# strobe_tuner.net
KiCad netlist of a schematic drawn in EAGLE
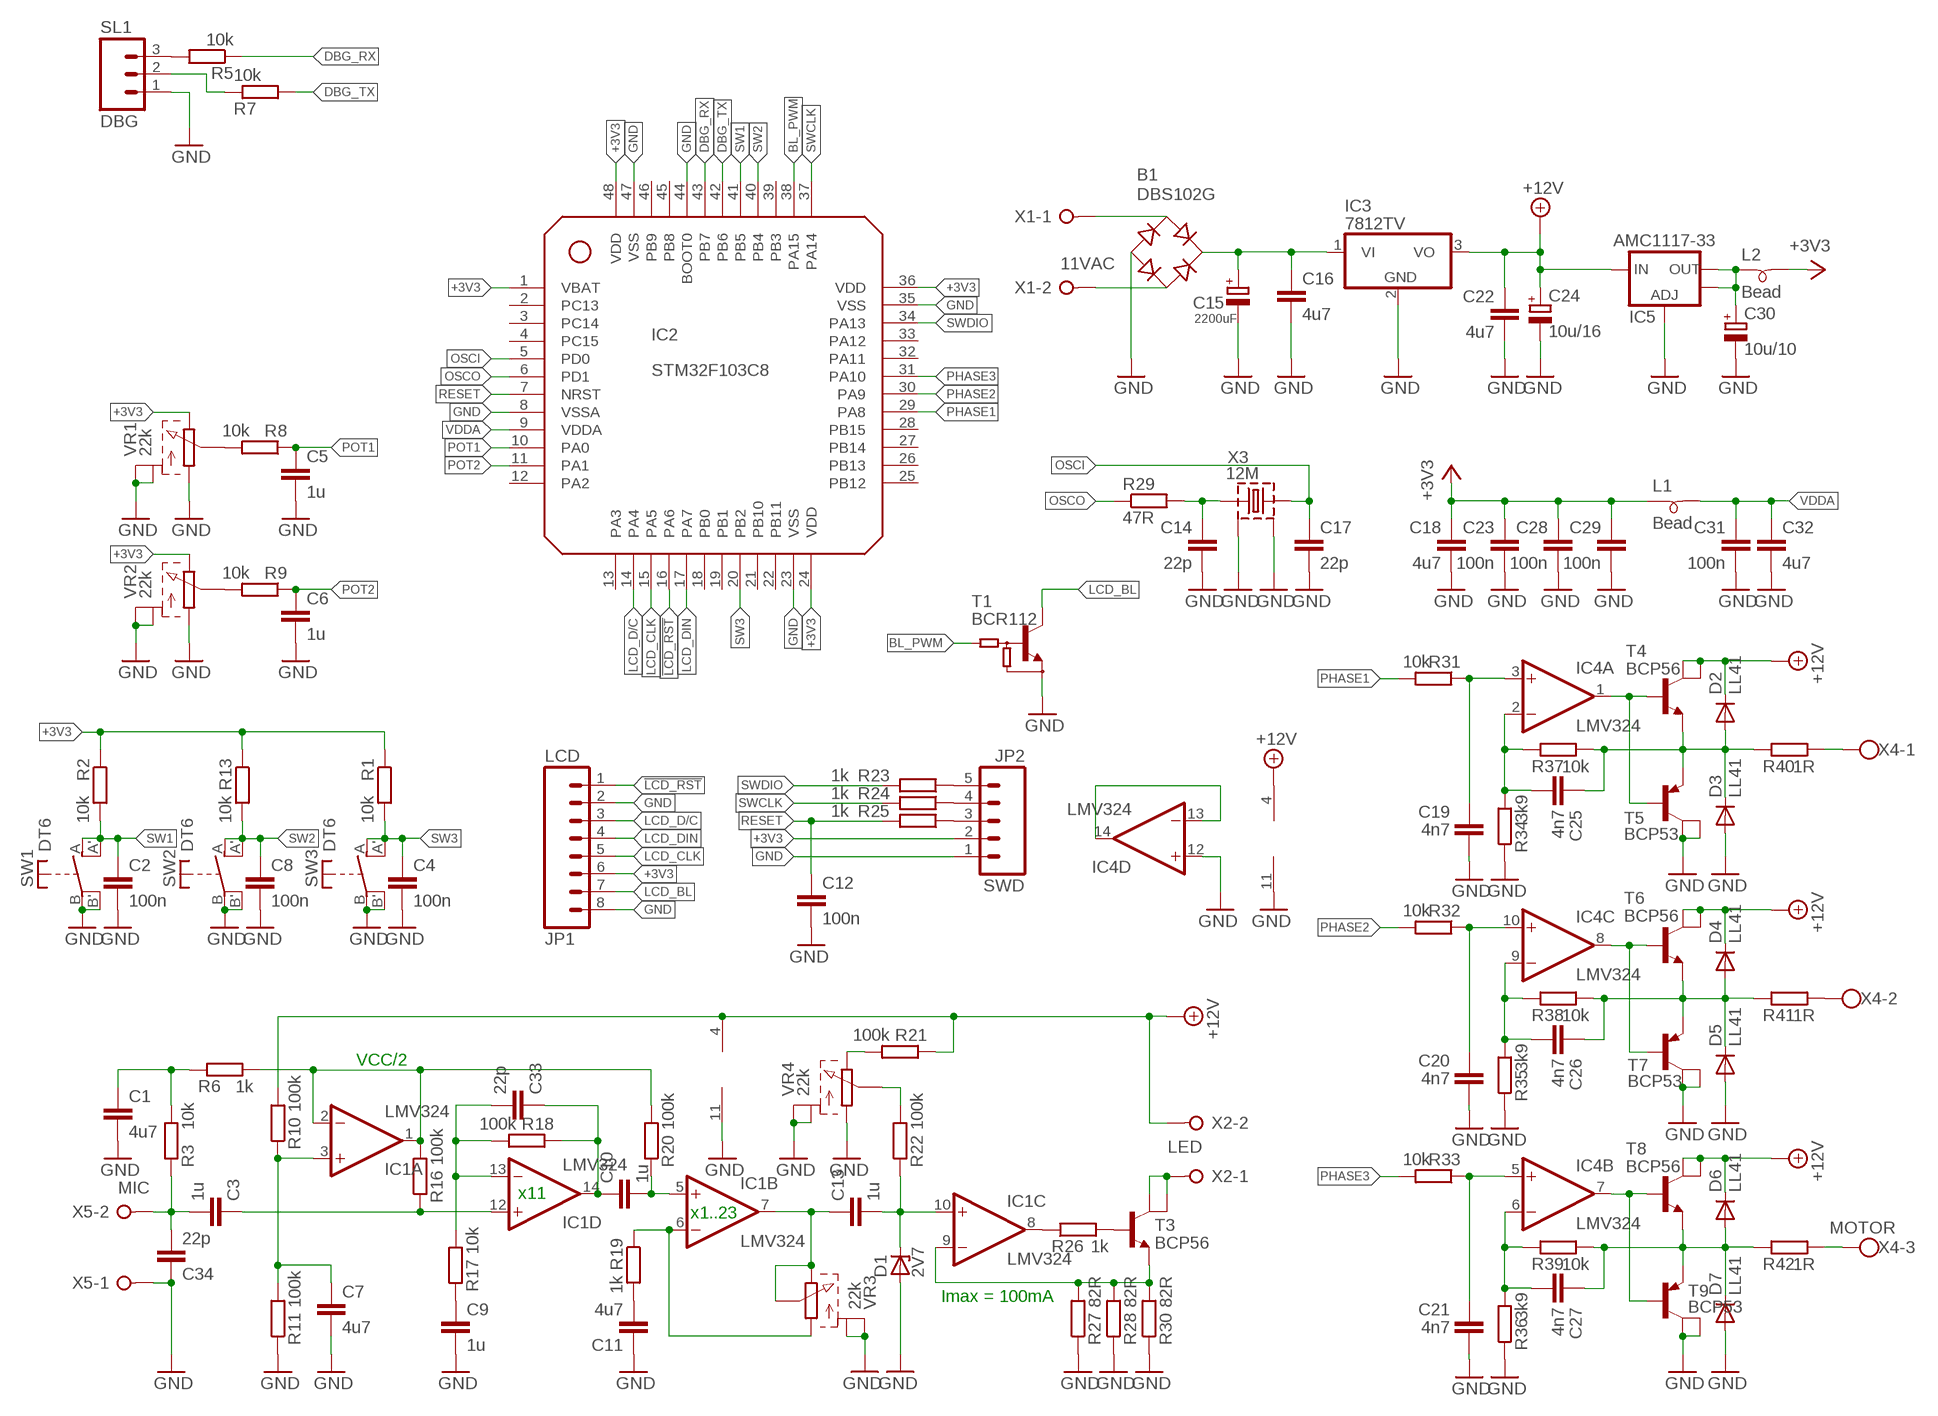
[diagram p0: schematic, sheet 1]

(export (version "E")
  (design (tool "Eeschema 10.0.6"))
  (components
    (comp (ref "B1")
      (value "DBS102G")
      (footprint "eagle-import:DBS")
      (libsource (lib "eagle-import") (part "DB?GS102"))
    )
    (comp (ref "C1")
      (value "4u7")
      (footprint "eagle-import:1206")
      (libsource (lib "eagle-import") (part "1206_CAP"))
    )
    (comp (ref "C2")
      (value "100n")
      (footprint "eagle-import:0805")
      (libsource (lib "eagle-import") (part "0805_CAP"))
    )
    (comp (ref "C3")
      (value "1u")
      (footprint "eagle-import:1206")
      (libsource (lib "eagle-import") (part "1206_CAP"))
    )
    (comp (ref "C4")
      (value "100n")
      (footprint "eagle-import:0805")
      (libsource (lib "eagle-import") (part "0805_CAP"))
    )
    (comp (ref "C5")
      (value "1u")
      (footprint "eagle-import:1206")
      (libsource (lib "eagle-import") (part "1206_CAP"))
    )
    (comp (ref "C6")
      (value "1u")
      (footprint "eagle-import:1206")
      (libsource (lib "eagle-import") (part "1206_CAP"))
    )
    (comp (ref "C7")
      (value "4u7")
      (footprint "eagle-import:1206")
      (libsource (lib "eagle-import") (part "1206_CAP"))
    )
    (comp (ref "C8")
      (value "100n")
      (footprint "eagle-import:0805")
      (libsource (lib "eagle-import") (part "0805_CAP"))
    )
    (comp (ref "C9")
      (value "1u")
      (footprint "eagle-import:1206")
      (libsource (lib "eagle-import") (part "1206_CAP"))
    )
    (comp (ref "C10")
      (value "1u")
      (footprint "eagle-import:1206")
      (libsource (lib "eagle-import") (part "1206_CAP"))
    )
    (comp (ref "C11")
      (value "4u7")
      (footprint "eagle-import:1206")
      (libsource (lib "eagle-import") (part "1206_CAP"))
    )
    (comp (ref "C12")
      (value "100n")
      (footprint "eagle-import:0805")
      (libsource (lib "eagle-import") (part "0805_CAP"))
    )
    (comp (ref "C13")
      (value "1u")
      (footprint "eagle-import:1206")
      (libsource (lib "eagle-import") (part "1206_CAP"))
    )
    (comp (ref "C14")
      (value "22p")
      (footprint "eagle-import:0805")
      (libsource (lib "eagle-import") (part "0805_CAP"))
    )
    (comp (ref "C15")
      (value "2200uF")
      (footprint "eagle-import:E5-13")
      (libsource (lib "eagle-import") (part "CPOL-EUE5-13"))
    )
    (comp (ref "C16")
      (value "4u7")
      (footprint "eagle-import:1206")
      (libsource (lib "eagle-import") (part "1206_CAP"))
    )
    (comp (ref "C17")
      (value "22p")
      (footprint "eagle-import:0805")
      (libsource (lib "eagle-import") (part "0805_CAP"))
    )
    (comp (ref "C18")
      (value "4u7")
      (footprint "eagle-import:1206")
      (libsource (lib "eagle-import") (part "1206_CAP"))
    )
    (comp (ref "C19")
      (value "4n7")
      (footprint "eagle-import:0805")
      (libsource (lib "eagle-import") (part "0805_CAP"))
    )
    (comp (ref "C20")
      (value "4n7")
      (footprint "eagle-import:0805")
      (libsource (lib "eagle-import") (part "0805_CAP"))
    )
    (comp (ref "C21")
      (value "4n7")
      (footprint "eagle-import:0805")
      (libsource (lib "eagle-import") (part "0805_CAP"))
    )
    (comp (ref "C22")
      (value "4u7")
      (footprint "eagle-import:1206")
      (libsource (lib "eagle-import") (part "1206_CAP"))
    )
    (comp (ref "C23")
      (value "100n")
      (footprint "eagle-import:0805")
      (libsource (lib "eagle-import") (part "0805_CAP"))
    )
    (comp (ref "C24")
      (value "10u/16")
      (footprint "eagle-import:B_3528-21W")
      (libsource (lib "eagle-import") (part "CPOL-EUB/3528-21W"))
    )
    (comp (ref "C25")
      (value "4n7")
      (footprint "eagle-import:0805")
      (libsource (lib "eagle-import") (part "0805_CAP"))
    )
    (comp (ref "C26")
      (value "4n7")
      (footprint "eagle-import:0805")
      (libsource (lib "eagle-import") (part "0805_CAP"))
    )
    (comp (ref "C27")
      (value "4n7")
      (footprint "eagle-import:0805")
      (libsource (lib "eagle-import") (part "0805_CAP"))
    )
    (comp (ref "C28")
      (value "100n")
      (footprint "eagle-import:0805")
      (libsource (lib "eagle-import") (part "0805_CAP"))
    )
    (comp (ref "C29")
      (value "100n")
      (footprint "eagle-import:0805")
      (libsource (lib "eagle-import") (part "0805_CAP"))
    )
    (comp (ref "C30")
      (value "10u/10")
      (footprint "eagle-import:A_3216-18R")
      (libsource (lib "eagle-import") (part "CPOL-EUA/3216-18R"))
    )
    (comp (ref "C31")
      (value "100n")
      (footprint "eagle-import:0805")
      (libsource (lib "eagle-import") (part "0805_CAP"))
    )
    (comp (ref "C32")
      (value "4u7")
      (footprint "eagle-import:1206")
      (libsource (lib "eagle-import") (part "1206_CAP"))
    )
    (comp (ref "C33")
      (value "22p")
      (footprint "eagle-import:0805")
      (libsource (lib "eagle-import") (part "0805_CAP"))
    )
    (comp (ref "C34")
      (value "22p")
      (footprint "eagle-import:0805")
      (libsource (lib "eagle-import") (part "0805_CAP"))
    )
    (comp (ref "D1")
      (value "2V7")
      (footprint "eagle-import:SOT23")
      (libsource (lib "eagle-import") (part "ZENER-DIODESOT23"))
    )
    (comp (ref "D2")
      (value "LL41")
      (footprint "eagle-import:SOD80C")
      (libsource (lib "eagle-import") (part "PMLL41SOD80C"))
    )
    (comp (ref "D3")
      (value "LL41")
      (footprint "eagle-import:SOD80C")
      (libsource (lib "eagle-import") (part "PMLL41SOD80C"))
    )
    (comp (ref "D4")
      (value "LL41")
      (footprint "eagle-import:SOD80C")
      (libsource (lib "eagle-import") (part "PMLL41SOD80C"))
    )
    (comp (ref "D5")
      (value "LL41")
      (footprint "eagle-import:SOD80C")
      (libsource (lib "eagle-import") (part "PMLL41SOD80C"))
    )
    (comp (ref "D6")
      (value "LL41")
      (footprint "eagle-import:SOD80C")
      (libsource (lib "eagle-import") (part "PMLL41SOD80C"))
    )
    (comp (ref "D7")
      (value "LL41")
      (footprint "eagle-import:SOD80C")
      (libsource (lib "eagle-import") (part "PMLL41SOD80C"))
    )
    (comp (ref "IC1")
      (value "LMV324")
      (footprint "eagle-import:SO14")
      (libsource (lib "eagle-import") (part "OPA4UA134"))
    )
    (comp (ref "IC2")
      (value "STM32F103C8")
      (footprint "eagle-import:LQFP48")
      (libsource (lib "eagle-import") (part "STM32F103C8"))
    )
    (comp (ref "IC3")
      (value "7812TV")
      (footprint "eagle-import:TO220V")
      (libsource (lib "eagle-import") (part "78TV12"))
    )
    (comp (ref "IC4")
      (value "LMV324")
      (footprint "eagle-import:SO14")
      (libsource (lib "eagle-import") (part "OPA4UA134"))
    )
    (comp (ref "IC5")
      (value "AMC1117-33")
      (footprint "eagle-import:SOT223")
      (libsource (lib "eagle-import") (part "V_REG_LM1117SOT223"))
    )
    (comp (ref "JP1")
      (value "LCD")
      (footprint "eagle-import:1X08")
      (libsource (lib "eagle-import") (part "M08"))
    )
    (comp (ref "JP2")
      (value "SWD")
      (footprint "eagle-import:1X05_LOCK_LONGPADS")
      (libsource (lib "eagle-import") (part "M05LOCK_LONGPADS"))
    )
    (comp (ref "L1")
      (value "Bead")
      (footprint "eagle-import:0805")
      (libsource (lib "eagle-import") (part "0805_IND"))
    )
    (comp (ref "L2")
      (value "Bead")
      (footprint "eagle-import:0805")
      (libsource (lib "eagle-import") (part "0805_IND"))
    )
    (comp (ref "R1")
      (value "10k")
      (footprint "eagle-import:0805")
      (libsource (lib "eagle-import") (part "0805_RES"))
    )
    (comp (ref "R2")
      (value "10k")
      (footprint "eagle-import:0805")
      (libsource (lib "eagle-import") (part "0805_RES"))
    )
    (comp (ref "R3")
      (value "10k")
      (footprint "eagle-import:0805")
      (libsource (lib "eagle-import") (part "0805_RES"))
    )
    (comp (ref "R5")
      (value "10k")
      (footprint "eagle-import:0805")
      (libsource (lib "eagle-import") (part "0805_RES"))
    )
    (comp (ref "R6")
      (value "1k")
      (footprint "eagle-import:0805")
      (libsource (lib "eagle-import") (part "0805_RES"))
    )
    (comp (ref "R7")
      (value "10k")
      (footprint "eagle-import:0805")
      (libsource (lib "eagle-import") (part "0805_RES"))
    )
    (comp (ref "R8")
      (value "10k")
      (footprint "eagle-import:0805")
      (libsource (lib "eagle-import") (part "0805_RES"))
    )
    (comp (ref "R9")
      (value "10k")
      (footprint "eagle-import:0805")
      (libsource (lib "eagle-import") (part "0805_RES"))
    )
    (comp (ref "R10")
      (value "100k")
      (footprint "eagle-import:0805")
      (libsource (lib "eagle-import") (part "0805_RES"))
    )
    (comp (ref "R11")
      (value "100k")
      (footprint "eagle-import:0805")
      (libsource (lib "eagle-import") (part "0805_RES"))
    )
    (comp (ref "R13")
      (value "10k")
      (footprint "eagle-import:0805")
      (libsource (lib "eagle-import") (part "0805_RES"))
    )
    (comp (ref "R16")
      (value "100k")
      (footprint "eagle-import:0805")
      (libsource (lib "eagle-import") (part "0805_RES"))
    )
    (comp (ref "R17")
      (value "10k")
      (footprint "eagle-import:0805")
      (libsource (lib "eagle-import") (part "0805_RES"))
    )
    (comp (ref "R18")
      (value "100k")
      (footprint "eagle-import:0805")
      (libsource (lib "eagle-import") (part "0805_RES"))
    )
    (comp (ref "R19")
      (value "1k")
      (footprint "eagle-import:0805")
      (libsource (lib "eagle-import") (part "0805_RES"))
    )
    (comp (ref "R20")
      (value "100k")
      (footprint "eagle-import:0805")
      (libsource (lib "eagle-import") (part "0805_RES"))
    )
    (comp (ref "R21")
      (value "100k")
      (footprint "eagle-import:0805")
      (libsource (lib "eagle-import") (part "0805_RES"))
    )
    (comp (ref "R22")
      (value "100k")
      (footprint "eagle-import:0805")
      (libsource (lib "eagle-import") (part "0805_RES"))
    )
    (comp (ref "R23")
      (value "1k")
      (footprint "eagle-import:0805")
      (libsource (lib "eagle-import") (part "0805_RES"))
    )
    (comp (ref "R24")
      (value "1k")
      (footprint "eagle-import:0805")
      (libsource (lib "eagle-import") (part "0805_RES"))
    )
    (comp (ref "R25")
      (value "1k")
      (footprint "eagle-import:0805")
      (libsource (lib "eagle-import") (part "0805_RES"))
    )
    (comp (ref "R26")
      (value "1k")
      (footprint "eagle-import:0805")
      (libsource (lib "eagle-import") (part "0805_RES"))
    )
    (comp (ref "R27")
      (value "82R")
      (footprint "eagle-import:0805")
      (libsource (lib "eagle-import") (part "0805_RES"))
    )
    (comp (ref "R28")
      (value "82R")
      (footprint "eagle-import:0805")
      (libsource (lib "eagle-import") (part "0805_RES"))
    )
    (comp (ref "R29")
      (value "47R")
      (footprint "eagle-import:0805")
      (libsource (lib "eagle-import") (part "0805_RES"))
    )
    (comp (ref "R30")
      (value "82R")
      (footprint "eagle-import:0805")
      (libsource (lib "eagle-import") (part "0805_RES"))
    )
    (comp (ref "R31")
      (value "10k")
      (footprint "eagle-import:0805")
      (libsource (lib "eagle-import") (part "0805_RES"))
    )
    (comp (ref "R32")
      (value "10k")
      (footprint "eagle-import:0805")
      (libsource (lib "eagle-import") (part "0805_RES"))
    )
    (comp (ref "R33")
      (value "10k")
      (footprint "eagle-import:0805")
      (libsource (lib "eagle-import") (part "0805_RES"))
    )
    (comp (ref "R34")
      (value "3k9")
      (footprint "eagle-import:0805")
      (libsource (lib "eagle-import") (part "0805_RES"))
    )
    (comp (ref "R35")
      (value "3k9")
      (footprint "eagle-import:0805")
      (libsource (lib "eagle-import") (part "0805_RES"))
    )
    (comp (ref "R36")
      (value "3k9")
      (footprint "eagle-import:0805")
      (libsource (lib "eagle-import") (part "0805_RES"))
    )
    (comp (ref "R37")
      (value "10k")
      (footprint "eagle-import:0805")
      (libsource (lib "eagle-import") (part "0805_RES"))
    )
    (comp (ref "R38")
      (value "10k")
      (footprint "eagle-import:0805")
      (libsource (lib "eagle-import") (part "0805_RES"))
    )
    (comp (ref "R39")
      (value "10k")
      (footprint "eagle-import:0805")
      (libsource (lib "eagle-import") (part "0805_RES"))
    )
    (comp (ref "R40")
      (value "1R")
      (footprint "eagle-import:0805")
      (libsource (lib "eagle-import") (part "0805_RES"))
    )
    (comp (ref "R41")
      (value "1R")
      (footprint "eagle-import:0805")
      (libsource (lib "eagle-import") (part "0805_RES"))
    )
    (comp (ref "R42")
      (value "1R")
      (footprint "eagle-import:0805")
      (libsource (lib "eagle-import") (part "0805_RES"))
    )
    (comp (ref "SL1")
      (value "DBG")
      (footprint "eagle-import:03P")
      (libsource (lib "eagle-import") (part "M03"))
    )
    (comp (ref "SW1")
      (value "DT6")
      (footprint "eagle-import:D6R")
      (libsource (lib "eagle-import") (part "TACTSW_DT6"))
    )
    (comp (ref "SW2")
      (value "DT6")
      (footprint "eagle-import:D6R")
      (libsource (lib "eagle-import") (part "TACTSW_DT6"))
    )
    (comp (ref "SW3")
      (value "DT6")
      (footprint "eagle-import:D6R")
      (libsource (lib "eagle-import") (part "TACTSW_DT6"))
    )
    (comp (ref "T1")
      (value "BCR112")
      (footprint "eagle-import:SOT23")
      (libsource (lib "eagle-import") (part "BCR112"))
    )
    (comp (ref "T3")
      (value "BCP56")
      (footprint "eagle-import:SOT223")
      (libsource (lib "eagle-import") (part "BCP56"))
    )
    (comp (ref "T4")
      (value "BCP56")
      (footprint "eagle-import:SOT223")
      (libsource (lib "eagle-import") (part "BCP56"))
    )
    (comp (ref "T5")
      (value "BCP53")
      (footprint "eagle-import:SOT223")
      (libsource (lib "eagle-import") (part "BCP53"))
    )
    (comp (ref "T6")
      (value "BCP56")
      (footprint "eagle-import:SOT223")
      (libsource (lib "eagle-import") (part "BCP56"))
    )
    (comp (ref "T7")
      (value "BCP53")
      (footprint "eagle-import:SOT223")
      (libsource (lib "eagle-import") (part "BCP53"))
    )
    (comp (ref "T8")
      (value "BCP56")
      (footprint "eagle-import:SOT223")
      (libsource (lib "eagle-import") (part "BCP56"))
    )
    (comp (ref "T9")
      (value "BCP53")
      (footprint "eagle-import:SOT223")
      (libsource (lib "eagle-import") (part "BCP53"))
    )
    (comp (ref "VR1")
      (value "22k")
      (footprint "eagle-import:R122KNP")
      (libsource (lib "eagle-import") (part "R122KNP"))
    )
    (comp (ref "VR2")
      (value "22k")
      (footprint "eagle-import:R122KNP")
      (libsource (lib "eagle-import") (part "R122KNP"))
    )
    (comp (ref "VR3")
      (value "22k")
      (footprint "eagle-import:R122KNP")
      (libsource (lib "eagle-import") (part "R122KNP"))
    )
    (comp (ref "VR4")
      (value "22k")
      (footprint "eagle-import:R122KNP")
      (libsource (lib "eagle-import") (part "R122KNP"))
    )
    (comp (ref "X1")
      (value "11VAC")
      (footprint "eagle-import:W237-132")
      (libsource (lib "eagle-import") (part "W237-02P"))
    )
    (comp (ref "X2")
      (value "LED")
      (footprint "eagle-import:W237-132")
      (libsource (lib "eagle-import") (part "W237-02P"))
    )
    (comp (ref "X3")
      (value "12M")
      (footprint "eagle-import:CPFX-104")
      (libsource (lib "eagle-import") (part "CPFX-104"))
    )
    (comp (ref "X4")
      (value "MOTOR")
      (footprint "eagle-import:W237-103")
      (fields (field (name "MPN") "237-103"))
      (libsource (lib "eagle-import") (part "W237-103"))
    )
    (comp (ref "X5")
      (value "MIC")
      (footprint "eagle-import:W237-132")
      (libsource (lib "eagle-import") (part "W237-02P"))
    )
  )
  (nets
    (net (code "1") (name "+3V3") (class "Default")
      (node (ref "C18") (pin "1") (pinfunction "1_1") (pintype "passive"))
      (node (ref "C23") (pin "1") (pinfunction "1_1") (pintype "passive"))
      (node (ref "C28") (pin "1") (pinfunction "1_1") (pintype "passive"))
      (node (ref "C29") (pin "1") (pinfunction "1_1") (pintype "passive"))
      (node (ref "IC2") (pin "1") (pinfunction "VBAT_1") (pintype "power_in"))
      (node (ref "IC2") (pin "24") (pinfunction "VDD_24") (pintype "power_in"))
      (node (ref "IC2") (pin "36") (pinfunction "VDD_36") (pintype "power_in"))
      (node (ref "IC2") (pin "48") (pinfunction "VDD_48") (pintype "power_in"))
      (node (ref "JP1") (pin "6") (pinfunction "6_6") (pintype "passive"))
      (node (ref "JP2") (pin "2") (pinfunction "2_2") (pintype "passive"))
      (node (ref "L1") (pin "2") (pinfunction "1_2") (pintype "passive"))
      (node (ref "L2") (pin "1") (pinfunction "2_1") (pintype "passive"))
      (node (ref "R1") (pin "1") (pinfunction "1_1") (pintype "passive"))
      (node (ref "R13") (pin "1") (pinfunction "1_1") (pintype "passive"))
      (node (ref "R2") (pin "1") (pinfunction "1_1") (pintype "passive"))
      (node (ref "VR1") (pin "CW") (pinfunction "E_CW") (pintype "passive"))
      (node (ref "VR2") (pin "CW") (pinfunction "E_CW") (pintype "passive"))
    )
    (net (code "2") (name "+12V") (class "Default")
      (node (ref "C22") (pin "1") (pinfunction "1_1") (pintype "passive"))
      (node (ref "C24") (pin "+") (pinfunction "+_+") (pintype "passive"))
      (node (ref "D2") (pin "C") (pinfunction "C_C") (pintype "passive"))
      (node (ref "D4") (pin "C") (pinfunction "C_C") (pintype "passive"))
      (node (ref "D6") (pin "C") (pinfunction "C_C") (pintype "passive"))
      (node (ref "IC1") (pin "4") (pinfunction "V+_4") (pintype "power_in"))
      (node (ref "IC3") (pin "3") (pinfunction "VO_3") (pintype "passive"))
      (node (ref "IC4") (pin "4") (pinfunction "V+_4") (pintype "power_in"))
      (node (ref "IC5") (pin "3") (pinfunction "IN_3") (pintype "input"))
      (node (ref "R10") (pin "2") (pinfunction "2_2") (pintype "passive"))
      (node (ref "R21") (pin "1") (pinfunction "1_1") (pintype "passive"))
      (node (ref "T4") (pin "2") (pinfunction "C_2") (pintype "passive"))
      (node (ref "T4") (pin "4") (pinfunction "C1_4") (pintype "passive"))
      (node (ref "T6") (pin "2") (pinfunction "C_2") (pintype "passive"))
      (node (ref "T6") (pin "4") (pinfunction "C1_4") (pintype "passive"))
      (node (ref "T8") (pin "2") (pinfunction "C_2") (pintype "passive"))
      (node (ref "T8") (pin "4") (pinfunction "C1_4") (pintype "passive"))
      (node (ref "X2") (pin "2") (pinfunction "KL_2") (pintype "passive"))
    )
    (net (code "3") (name "/~{LCD_RST}") (class "Default")
      (node (ref "IC2") (pin "16") (pinfunction "PA6_16") (pintype "bidirectional"))
      (node (ref "JP1") (pin "1") (pinfunction "1_1") (pintype "passive"))
    )
    (net (code "4") (name "BL_PWM") (class "Default")
      (node (ref "IC2") (pin "38") (pinfunction "PA15_38") (pintype "bidirectional"))
      (node (ref "T1") (pin "1") (pinfunction "B_1") (pintype "passive"))
    )
    (net (code "5") (name "DBG_RX") (class "Default")
      (node (ref "IC2") (pin "43") (pinfunction "PB7_43") (pintype "bidirectional"))
      (node (ref "R5") (pin "1") (pinfunction "1_1") (pintype "passive"))
    )
    (net (code "6") (name "DBG_TX") (class "Default")
      (node (ref "IC2") (pin "42") (pinfunction "PB6_42") (pintype "bidirectional"))
      (node (ref "R7") (pin "2") (pinfunction "2_2") (pintype "passive"))
    )
    (net (code "7") (name "GND") (class "Default")
      (node (ref "B1") (pin "-") (pinfunction "-_-") (pintype "passive"))
      (node (ref "C1") (pin "2") (pinfunction "2_2") (pintype "passive"))
      (node (ref "C11") (pin "1") (pinfunction "1_1") (pintype "passive"))
      (node (ref "C12") (pin "2") (pinfunction "2_2") (pintype "passive"))
      (node (ref "C14") (pin "2") (pinfunction "2_2") (pintype "passive"))
      (node (ref "C15") (pin "-") (pinfunction "-_-") (pintype "passive"))
      (node (ref "C16") (pin "2") (pinfunction "2_2") (pintype "passive"))
      (node (ref "C17") (pin "2") (pinfunction "2_2") (pintype "passive"))
      (node (ref "C18") (pin "2") (pinfunction "2_2") (pintype "passive"))
      (node (ref "C19") (pin "2") (pinfunction "2_2") (pintype "passive"))
      (node (ref "C2") (pin "2") (pinfunction "2_2") (pintype "passive"))
      (node (ref "C20") (pin "2") (pinfunction "2_2") (pintype "passive"))
      (node (ref "C21") (pin "2") (pinfunction "2_2") (pintype "passive"))
      (node (ref "C22") (pin "2") (pinfunction "2_2") (pintype "passive"))
      (node (ref "C23") (pin "2") (pinfunction "2_2") (pintype "passive"))
      (node (ref "C24") (pin "-") (pinfunction "-_-") (pintype "passive"))
      (node (ref "C28") (pin "2") (pinfunction "2_2") (pintype "passive"))
      (node (ref "C29") (pin "2") (pinfunction "2_2") (pintype "passive"))
      (node (ref "C30") (pin "-") (pinfunction "-_-") (pintype "passive"))
      (node (ref "C31") (pin "2") (pinfunction "2_2") (pintype "passive"))
      (node (ref "C32") (pin "2") (pinfunction "2_2") (pintype "passive"))
      (node (ref "C34") (pin "1") (pinfunction "1_1") (pintype "passive"))
      (node (ref "C4") (pin "2") (pinfunction "2_2") (pintype "passive"))
      (node (ref "C5") (pin "2") (pinfunction "2_2") (pintype "passive"))
      (node (ref "C6") (pin "2") (pinfunction "2_2") (pintype "passive"))
      (node (ref "C7") (pin "2") (pinfunction "2_2") (pintype "passive"))
      (node (ref "C8") (pin "2") (pinfunction "2_2") (pintype "passive"))
      (node (ref "C9") (pin "2") (pinfunction "2_2") (pintype "passive"))
      (node (ref "D1") (pin "1") (pinfunction "A_1") (pintype "passive"))
      (node (ref "D3") (pin "A") (pinfunction "A_A") (pintype "passive"))
      (node (ref "D5") (pin "A") (pinfunction "A_A") (pintype "passive"))
      (node (ref "D7") (pin "A") (pinfunction "A_A") (pintype "passive"))
      (node (ref "IC1") (pin "11") (pinfunction "V-_11") (pintype "power_in"))
      (node (ref "IC2") (pin "23") (pinfunction "VSS_23") (pintype "power_in"))
      (node (ref "IC2") (pin "35") (pinfunction "VSS_35") (pintype "power_in"))
      (node (ref "IC2") (pin "44") (pinfunction "BOOT0_44") (pintype "bidirectional"))
      (node (ref "IC2") (pin "47") (pinfunction "VSS_47") (pintype "power_in"))
      (node (ref "IC2") (pin "8") (pinfunction "VSSA_8") (pintype "power_in"))
      (node (ref "IC3") (pin "2") (pinfunction "GND_2") (pintype "passive"))
      (node (ref "IC4") (pin "11") (pinfunction "V-_11") (pintype "power_in"))
      (node (ref "IC4") (pin "12") (pinfunction "+IN_12") (pintype "input"))
      (node (ref "IC5") (pin "1") (pinfunction "ADJ_1") (pintype "input"))
      (node (ref "JP1") (pin "2") (pinfunction "2_2") (pintype "passive"))
      (node (ref "JP1") (pin "8") (pinfunction "8_8") (pintype "passive"))
      (node (ref "JP2") (pin "1") (pinfunction "1_1") (pintype "passive"))
      (node (ref "R11") (pin "1") (pinfunction "1_1") (pintype "passive"))
      (node (ref "R27") (pin "1") (pinfunction "1_1") (pintype "passive"))
      (node (ref "R28") (pin "1") (pinfunction "1_1") (pintype "passive"))
      (node (ref "R30") (pin "1") (pinfunction "1_1") (pintype "passive"))
      (node (ref "R34") (pin "1") (pinfunction "1_1") (pintype "passive"))
      (node (ref "R35") (pin "1") (pinfunction "1_1") (pintype "passive"))
      (node (ref "R36") (pin "1") (pinfunction "1_1") (pintype "passive"))
      (node (ref "SL1") (pin "1") (pinfunction "1_1") (pintype "passive"))
      (node (ref "SW1") (pin "B") (pinfunction "B1_B") (pintype "passive"))
      (node (ref "SW1") (pin "B'") (pinfunction "B2_B'") (pintype "passive"))
      (node (ref "SW2") (pin "B") (pinfunction "B1_B") (pintype "passive"))
      (node (ref "SW2") (pin "B'") (pinfunction "B2_B'") (pintype "passive"))
      (node (ref "SW3") (pin "B") (pinfunction "B1_B") (pintype "passive"))
      (node (ref "SW3") (pin "B'") (pinfunction "B2_B'") (pintype "passive"))
      (node (ref "T1") (pin "2") (pinfunction "E_2") (pintype "passive"))
      (node (ref "T5") (pin "2") (pinfunction "C_2") (pintype "passive"))
      (node (ref "T5") (pin "4") (pinfunction "C1_4") (pintype "passive"))
      (node (ref "T7") (pin "2") (pinfunction "C_2") (pintype "passive"))
      (node (ref "T7") (pin "4") (pinfunction "C1_4") (pintype "passive"))
      (node (ref "T9") (pin "2") (pinfunction "C_2") (pintype "passive"))
      (node (ref "T9") (pin "4") (pinfunction "C1_4") (pintype "passive"))
      (node (ref "VR1") (pin "CCW") (pinfunction "A_CCW") (pintype "passive"))
      (node (ref "VR1") (pin "P$1") (pinfunction "CASE1_P$1") (pintype "passive"))
      (node (ref "VR1") (pin "P$2") (pinfunction "CASE2_P$2") (pintype "passive"))
      (node (ref "VR2") (pin "CCW") (pinfunction "A_CCW") (pintype "passive"))
      (node (ref "VR2") (pin "P$1") (pinfunction "CASE1_P$1") (pintype "passive"))
      (node (ref "VR2") (pin "P$2") (pinfunction "CASE2_P$2") (pintype "passive"))
      (node (ref "VR3") (pin "P$1") (pinfunction "CASE1_P$1") (pintype "passive"))
      (node (ref "VR3") (pin "P$2") (pinfunction "CASE2_P$2") (pintype "passive"))
      (node (ref "VR4") (pin "CCW") (pinfunction "A_CCW") (pintype "passive"))
      (node (ref "VR4") (pin "P$1") (pinfunction "CASE1_P$1") (pintype "passive"))
      (node (ref "VR4") (pin "P$2") (pinfunction "CASE2_P$2") (pintype "passive"))
      (node (ref "X3") (pin "2") (pinfunction "G1_2") (pintype "passive"))
      (node (ref "X3") (pin "4") (pinfunction "G2_4") (pintype "passive"))
      (node (ref "X5") (pin "1") (pinfunction "KL_1") (pintype "passive"))
    )
    (net (code "8") (name "LCD_BL") (class "Default")
      (node (ref "JP1") (pin "7") (pinfunction "7_7") (pintype "passive"))
      (node (ref "T1") (pin "3") (pinfunction "C_3") (pintype "passive"))
    )
    (net (code "9") (name "LCD_CLK") (class "Default")
      (node (ref "IC2") (pin "15") (pinfunction "PA5_15") (pintype "bidirectional"))
      (node (ref "JP1") (pin "5") (pinfunction "5_5") (pintype "passive"))
    )
    (net (code "10") (name "LCD_DIN") (class "Default")
      (node (ref "IC2") (pin "17") (pinfunction "PA7_17") (pintype "bidirectional"))
      (node (ref "JP1") (pin "4") (pinfunction "4_4") (pintype "passive"))
    )
    (net (code "11") (name "LCD_D{slash}C") (class "Default")
      (node (ref "IC2") (pin "14") (pinfunction "PA4_14") (pintype "bidirectional"))
      (node (ref "JP1") (pin "3") (pinfunction "3_3") (pintype "passive"))
    )
    (net (code "12") (name "Net-(C1-Pad1)") (class "Default")
      (node (ref "C1") (pin "1") (pinfunction "1_1") (pintype "passive"))
      (node (ref "R3") (pin "2") (pinfunction "2_2") (pintype "passive"))
      (node (ref "R6") (pin "1") (pinfunction "1_1") (pintype "passive"))
    )
    (net (code "13") (name "Net-(C9-Pad1)") (class "Default")
      (node (ref "C9") (pin "1") (pinfunction "1_1") (pintype "passive"))
      (node (ref "R17") (pin "1") (pinfunction "1_1") (pintype "passive"))
    )
    (net (code "14") (name "Net-(C11-Pad2)") (class "Default")
      (node (ref "C11") (pin "2") (pinfunction "2_2") (pintype "passive"))
      (node (ref "R19") (pin "2") (pinfunction "2_2") (pintype "passive"))
    )
    (net (code "15") (name "Net-(C14-Pad1)") (class "Default")
      (node (ref "C14") (pin "1") (pinfunction "1_1") (pintype "passive"))
      (node (ref "R29") (pin "2") (pinfunction "2_2") (pintype "passive"))
      (node (ref "X3") (pin "1") (pinfunction "1_1") (pintype "passive"))
    )
    (net (code "16") (name "Net-(D1-C)") (class "Default")
      (node (ref "C13") (pin "2") (pinfunction "2_2") (pintype "passive"))
      (node (ref "D1") (pin "3") (pinfunction "C_3") (pintype "passive"))
      (node (ref "IC1") (pin "10") (pinfunction "+IN_10") (pintype "input"))
      (node (ref "R22") (pin "1") (pinfunction "1_1") (pintype "passive"))
    )
    (net (code "17") (name "Net-(IC1A-+IN)") (class "Default")
      (node (ref "C7") (pin "1") (pinfunction "1_1") (pintype "passive"))
      (node (ref "IC1") (pin "3") (pinfunction "+IN_3") (pintype "input"))
      (node (ref "R10") (pin "1") (pinfunction "1_1") (pintype "passive"))
      (node (ref "R11") (pin "2") (pinfunction "2_2") (pintype "passive"))
    )
    (net (code "18") (name "Net-(IC1A--IN)") (class "Default")
      (node (ref "IC1") (pin "1") (pinfunction "OUT_1") (pintype "output"))
      (node (ref "IC1") (pin "2") (pinfunction "-IN_2") (pintype "input"))
      (node (ref "R16") (pin "2") (pinfunction "2_2") (pintype "passive"))
      (node (ref "R20") (pin "2") (pinfunction "2_2") (pintype "passive"))
      (node (ref "R6") (pin "2") (pinfunction "2_2") (pintype "passive"))
    )
    (net (code "19") (name "Net-(IC1B-+IN)") (class "Default")
      (node (ref "C10") (pin "2") (pinfunction "2_2") (pintype "passive"))
      (node (ref "IC1") (pin "5") (pinfunction "+IN_5") (pintype "input"))
      (node (ref "R20") (pin "1") (pinfunction "1_1") (pintype "passive"))
    )
    (net (code "20") (name "Net-(IC1B--IN)") (class "Default")
      (node (ref "IC1") (pin "6") (pinfunction "-IN_6") (pintype "input"))
      (node (ref "R19") (pin "1") (pinfunction "1_1") (pintype "passive"))
      (node (ref "VR3") (pin "CCW") (pinfunction "A_CCW") (pintype "passive"))
    )
    (net (code "21") (name "Net-(IC1B-OUT)") (class "Default")
      (node (ref "C13") (pin "1") (pinfunction "1_1") (pintype "passive"))
      (node (ref "IC1") (pin "7") (pinfunction "OUT_7") (pintype "output"))
      (node (ref "VR3") (pin "CW") (pinfunction "E_CW") (pintype "passive"))
      (node (ref "VR3") (pin "SLIDER") (pinfunction "S_SLIDER") (pintype "passive"))
    )
    (net (code "22") (name "Net-(IC1C--IN)") (class "Default")
      (node (ref "IC1") (pin "9") (pinfunction "-IN_9") (pintype "input"))
      (node (ref "R27") (pin "2") (pinfunction "2_2") (pintype "passive"))
      (node (ref "R28") (pin "2") (pinfunction "2_2") (pintype "passive"))
      (node (ref "R30") (pin "2") (pinfunction "2_2") (pintype "passive"))
      (node (ref "T3") (pin "3") (pinfunction "E_3") (pintype "passive"))
    )
    (net (code "23") (name "Net-(IC1C-OUT)") (class "Default")
      (node (ref "IC1") (pin "8") (pinfunction "OUT_8") (pintype "output"))
      (node (ref "R26") (pin "1") (pinfunction "1_1") (pintype "passive"))
    )
    (net (code "24") (name "Net-(IC1D-+IN)") (class "Default")
      (node (ref "C3") (pin "1") (pinfunction "1_1") (pintype "passive"))
      (node (ref "IC1") (pin "12") (pinfunction "+IN_12") (pintype "input"))
      (node (ref "R16") (pin "1") (pinfunction "1_1") (pintype "passive"))
    )
    (net (code "25") (name "Net-(IC1D--IN)") (class "Default")
      (node (ref "C33") (pin "2") (pinfunction "2_2") (pintype "passive"))
      (node (ref "IC1") (pin "13") (pinfunction "-IN_13") (pintype "input"))
      (node (ref "R17") (pin "2") (pinfunction "2_2") (pintype "passive"))
      (node (ref "R18") (pin "2") (pinfunction "2_2") (pintype "passive"))
    )
    (net (code "26") (name "Net-(IC1D-OUT)") (class "Default")
      (node (ref "C10") (pin "1") (pinfunction "1_1") (pintype "passive"))
      (node (ref "C33") (pin "1") (pinfunction "1_1") (pintype "passive"))
      (node (ref "IC1") (pin "14") (pinfunction "OUT_14") (pintype "output"))
      (node (ref "R18") (pin "1") (pinfunction "1_1") (pintype "passive"))
    )
    (net (code "27") (name "Net-(IC3-VI)") (class "Default")
      (node (ref "B1") (pin "+") (pinfunction "+_+") (pintype "passive"))
      (node (ref "C15") (pin "+") (pinfunction "+_+") (pintype "passive"))
      (node (ref "C16") (pin "1") (pinfunction "1_1") (pintype "passive"))
      (node (ref "IC3") (pin "1") (pinfunction "VI_1") (pintype "input"))
    )
    (net (code "28") (name "Net-(IC4A-+IN)") (class "Default")
      (node (ref "C19") (pin "1") (pinfunction "1_1") (pintype "passive"))
      (node (ref "IC4") (pin "3") (pinfunction "+IN_3") (pintype "input"))
      (node (ref "R31") (pin "1") (pinfunction "1_1") (pintype "passive"))
    )
    (net (code "29") (name "Net-(IC4A--IN)") (class "Default")
      (node (ref "C25") (pin "2") (pinfunction "2_2") (pintype "passive"))
      (node (ref "IC4") (pin "2") (pinfunction "-IN_2") (pintype "input"))
      (node (ref "R34") (pin "2") (pinfunction "2_2") (pintype "passive"))
      (node (ref "R37") (pin "1") (pinfunction "1_1") (pintype "passive"))
    )
    (net (code "30") (name "Net-(IC4A-OUT)") (class "Default")
      (node (ref "IC4") (pin "1") (pinfunction "OUT_1") (pintype "output"))
      (node (ref "T4") (pin "1") (pinfunction "B_1") (pintype "passive"))
      (node (ref "T5") (pin "1") (pinfunction "B_1") (pintype "passive"))
    )
    (net (code "31") (name "Net-(IC4B-+IN)") (class "Default")
      (node (ref "C21") (pin "1") (pinfunction "1_1") (pintype "passive"))
      (node (ref "IC4") (pin "5") (pinfunction "+IN_5") (pintype "input"))
      (node (ref "R33") (pin "1") (pinfunction "1_1") (pintype "passive"))
    )
    (net (code "32") (name "Net-(IC4B--IN)") (class "Default")
      (node (ref "C27") (pin "2") (pinfunction "2_2") (pintype "passive"))
      (node (ref "IC4") (pin "6") (pinfunction "-IN_6") (pintype "input"))
      (node (ref "R36") (pin "2") (pinfunction "2_2") (pintype "passive"))
      (node (ref "R39") (pin "1") (pinfunction "1_1") (pintype "passive"))
    )
    (net (code "33") (name "Net-(IC4B-OUT)") (class "Default")
      (node (ref "IC4") (pin "7") (pinfunction "OUT_7") (pintype "output"))
      (node (ref "T8") (pin "1") (pinfunction "B_1") (pintype "passive"))
      (node (ref "T9") (pin "1") (pinfunction "B_1") (pintype "passive"))
    )
    (net (code "34") (name "Net-(IC4C-+IN)") (class "Default")
      (node (ref "C20") (pin "1") (pinfunction "1_1") (pintype "passive"))
      (node (ref "IC4") (pin "10") (pinfunction "+IN_10") (pintype "input"))
      (node (ref "R32") (pin "1") (pinfunction "1_1") (pintype "passive"))
    )
    (net (code "35") (name "Net-(IC4C--IN)") (class "Default")
      (node (ref "C26") (pin "2") (pinfunction "2_2") (pintype "passive"))
      (node (ref "IC4") (pin "9") (pinfunction "-IN_9") (pintype "input"))
      (node (ref "R35") (pin "2") (pinfunction "2_2") (pintype "passive"))
      (node (ref "R38") (pin "1") (pinfunction "1_1") (pintype "passive"))
    )
    (net (code "36") (name "Net-(IC4C-OUT)") (class "Default")
      (node (ref "IC4") (pin "8") (pinfunction "OUT_8") (pintype "output"))
      (node (ref "T6") (pin "1") (pinfunction "B_1") (pintype "passive"))
      (node (ref "T7") (pin "1") (pinfunction "B_1") (pintype "passive"))
    )
    (net (code "37") (name "Net-(IC4D--IN)") (class "Default")
      (node (ref "IC4") (pin "13") (pinfunction "-IN_13") (pintype "input"))
      (node (ref "IC4") (pin "14") (pinfunction "OUT_14") (pintype "output"))
    )
    (net (code "38") (name "Net-(JP2-Pad3)") (class "Default")
      (node (ref "JP2") (pin "3") (pinfunction "3_3") (pintype "passive"))
      (node (ref "R25") (pin "1") (pinfunction "1_1") (pintype "passive"))
    )
    (net (code "39") (name "Net-(JP2-Pad4)") (class "Default")
      (node (ref "JP2") (pin "4") (pinfunction "4_4") (pintype "passive"))
      (node (ref "R24") (pin "1") (pinfunction "1_1") (pintype "passive"))
    )
    (net (code "40") (name "Net-(JP2-Pad5)") (class "Default")
      (node (ref "JP2") (pin "5") (pinfunction "5_5") (pintype "passive"))
      (node (ref "R23") (pin "1") (pinfunction "1_1") (pintype "passive"))
    )
    (net (code "41") (name "Net-(L2-1)") (class "Default")
      (node (ref "C30") (pin "+") (pinfunction "+_+") (pintype "passive"))
      (node (ref "IC5") (pin "2") (pinfunction "OUT_2") (pintype "bidirectional"))
      (node (ref "IC5") (pin "4") (pinfunction "OUT_4") (pintype "bidirectional"))
      (node (ref "L2") (pin "2") (pinfunction "1_2") (pintype "passive"))
    )
    (net (code "42") (name "Net-(R5-Pad2)") (class "Default")
      (node (ref "R5") (pin "2") (pinfunction "2_2") (pintype "passive"))
      (node (ref "SL1") (pin "3") (pinfunction "3_3") (pintype "passive"))
    )
    (net (code "43") (name "Net-(R7-Pad1)") (class "Default")
      (node (ref "R7") (pin "1") (pinfunction "1_1") (pintype "passive"))
      (node (ref "SL1") (pin "2") (pinfunction "2_2") (pintype "passive"))
    )
    (net (code "44") (name "Net-(T3-B)") (class "Default")
      (node (ref "R26") (pin "2") (pinfunction "2_2") (pintype "passive"))
      (node (ref "T3") (pin "1") (pinfunction "B_1") (pintype "passive"))
    )
    (net (code "45") (name "Net-(T3-C)") (class "Default")
      (node (ref "T3") (pin "2") (pinfunction "C_2") (pintype "passive"))
      (node (ref "T3") (pin "4") (pinfunction "C1_4") (pintype "passive"))
      (node (ref "X2") (pin "1") (pinfunction "KL_1") (pintype "passive"))
    )
    (net (code "46") (name "Net-(T4-E)") (class "Default")
      (node (ref "C25") (pin "1") (pinfunction "1_1") (pintype "passive"))
      (node (ref "D2") (pin "A") (pinfunction "A_A") (pintype "passive"))
      (node (ref "D3") (pin "C") (pinfunction "C_C") (pintype "passive"))
      (node (ref "R37") (pin "2") (pinfunction "2_2") (pintype "passive"))
      (node (ref "R40") (pin "1") (pinfunction "1_1") (pintype "passive"))
      (node (ref "T4") (pin "3") (pinfunction "E_3") (pintype "passive"))
      (node (ref "T5") (pin "3") (pinfunction "E_3") (pintype "passive"))
    )
    (net (code "47") (name "Net-(T6-E)") (class "Default")
      (node (ref "C26") (pin "1") (pinfunction "1_1") (pintype "passive"))
      (node (ref "D4") (pin "A") (pinfunction "A_A") (pintype "passive"))
      (node (ref "D5") (pin "C") (pinfunction "C_C") (pintype "passive"))
      (node (ref "R38") (pin "2") (pinfunction "2_2") (pintype "passive"))
      (node (ref "R41") (pin "1") (pinfunction "1_1") (pintype "passive"))
      (node (ref "T6") (pin "3") (pinfunction "E_3") (pintype "passive"))
      (node (ref "T7") (pin "3") (pinfunction "E_3") (pintype "passive"))
    )
    (net (code "48") (name "Net-(T8-E)") (class "Default")
      (node (ref "C27") (pin "1") (pinfunction "1_1") (pintype "passive"))
      (node (ref "D6") (pin "A") (pinfunction "A_A") (pintype "passive"))
      (node (ref "D7") (pin "C") (pinfunction "C_C") (pintype "passive"))
      (node (ref "R39") (pin "2") (pinfunction "2_2") (pintype "passive"))
      (node (ref "R42") (pin "1") (pinfunction "1_1") (pintype "passive"))
      (node (ref "T8") (pin "3") (pinfunction "E_3") (pintype "passive"))
      (node (ref "T9") (pin "3") (pinfunction "E_3") (pintype "passive"))
    )
    (net (code "49") (name "Net-(VR1-S)") (class "Default")
      (node (ref "R8") (pin "2") (pinfunction "2_2") (pintype "passive"))
      (node (ref "VR1") (pin "SLIDER") (pinfunction "S_SLIDER") (pintype "passive"))
    )
    (net (code "50") (name "Net-(VR2-S)") (class "Default")
      (node (ref "R9") (pin "2") (pinfunction "2_2") (pintype "passive"))
      (node (ref "VR2") (pin "SLIDER") (pinfunction "S_SLIDER") (pintype "passive"))
    )
    (net (code "51") (name "Net-(VR4-E)") (class "Default")
      (node (ref "R21") (pin "2") (pinfunction "2_2") (pintype "passive"))
      (node (ref "VR4") (pin "CW") (pinfunction "E_CW") (pintype "passive"))
    )
    (net (code "52") (name "Net-(VR4-S)") (class "Default")
      (node (ref "R22") (pin "2") (pinfunction "2_2") (pintype "passive"))
      (node (ref "VR4") (pin "SLIDER") (pinfunction "S_SLIDER") (pintype "passive"))
    )
    (net (code "53") (name "Net-(X1A-KL)") (class "Default")
      (node (ref "B1") (pin "AC1") (pinfunction "AC1_AC1") (pintype "passive"))
      (node (ref "X1") (pin "1") (pinfunction "KL_1") (pintype "passive"))
    )
    (net (code "54") (name "Net-(X1B-KL)") (class "Default")
      (node (ref "B1") (pin "AC2") (pinfunction "AC2_AC2") (pintype "passive"))
      (node (ref "X1") (pin "2") (pinfunction "KL_2") (pintype "passive"))
    )
    (net (code "55") (name "Net-(X4A-KL)") (class "Default")
      (node (ref "R40") (pin "2") (pinfunction "2_2") (pintype "passive"))
      (node (ref "X4") (pin "1") (pinfunction "KL_1") (pintype "passive"))
    )
    (net (code "56") (name "Net-(X4B-KL)") (class "Default")
      (node (ref "R41") (pin "2") (pinfunction "2_2") (pintype "passive"))
      (node (ref "X4") (pin "2") (pinfunction "KL_2") (pintype "passive"))
    )
    (net (code "57") (name "Net-(X4C-KL)") (class "Default")
      (node (ref "R42") (pin "2") (pinfunction "2_2") (pintype "passive"))
      (node (ref "X4") (pin "3") (pinfunction "KL_3") (pintype "passive"))
    )
    (net (code "58") (name "Net-(X5B-KL)") (class "Default")
      (node (ref "C3") (pin "2") (pinfunction "2_2") (pintype "passive"))
      (node (ref "C34") (pin "2") (pinfunction "2_2") (pintype "passive"))
      (node (ref "R3") (pin "1") (pinfunction "1_1") (pintype "passive"))
      (node (ref "X5") (pin "2") (pinfunction "KL_2") (pintype "passive"))
    )
    (net (code "59") (name "OSCI") (class "Default")
      (node (ref "C17") (pin "1") (pinfunction "1_1") (pintype "passive"))
      (node (ref "IC2") (pin "5") (pinfunction "PD0_5") (pintype "bidirectional"))
      (node (ref "X3") (pin "3") (pinfunction "2_3") (pintype "passive"))
    )
    (net (code "60") (name "OSCO") (class "Default")
      (node (ref "IC2") (pin "6") (pinfunction "PD1_6") (pintype "bidirectional"))
      (node (ref "R29") (pin "1") (pinfunction "1_1") (pintype "passive"))
    )
    (net (code "61") (name "PHASE1") (class "Default")
      (node (ref "IC2") (pin "29") (pinfunction "PA8_29") (pintype "bidirectional"))
      (node (ref "R31") (pin "2") (pinfunction "2_2") (pintype "passive"))
    )
    (net (code "62") (name "PHASE2") (class "Default")
      (node (ref "IC2") (pin "30") (pinfunction "PA9_30") (pintype "bidirectional"))
      (node (ref "R32") (pin "2") (pinfunction "2_2") (pintype "passive"))
    )
    (net (code "63") (name "PHASE3") (class "Default")
      (node (ref "IC2") (pin "31") (pinfunction "PA10_31") (pintype "bidirectional"))
      (node (ref "R33") (pin "2") (pinfunction "2_2") (pintype "passive"))
    )
    (net (code "64") (name "POT1") (class "Default")
      (node (ref "C5") (pin "1") (pinfunction "1_1") (pintype "passive"))
      (node (ref "IC2") (pin "10") (pinfunction "PA0_10") (pintype "bidirectional"))
      (node (ref "R8") (pin "1") (pinfunction "1_1") (pintype "passive"))
    )
    (net (code "65") (name "POT2") (class "Default")
      (node (ref "C6") (pin "1") (pinfunction "1_1") (pintype "passive"))
      (node (ref "IC2") (pin "11") (pinfunction "PA1_11") (pintype "bidirectional"))
      (node (ref "R9") (pin "1") (pinfunction "1_1") (pintype "passive"))
    )
    (net (code "66") (name "RESET") (class "Default")
      (node (ref "C12") (pin "1") (pinfunction "1_1") (pintype "passive"))
      (node (ref "IC2") (pin "7") (pinfunction "NRST_7") (pintype "bidirectional"))
      (node (ref "R25") (pin "2") (pinfunction "2_2") (pintype "passive"))
    )
    (net (code "67") (name "SW1") (class "Default")
      (node (ref "C2") (pin "1") (pinfunction "1_1") (pintype "passive"))
      (node (ref "IC2") (pin "41") (pinfunction "PB5_41") (pintype "bidirectional"))
      (node (ref "R2") (pin "2") (pinfunction "2_2") (pintype "passive"))
      (node (ref "SW1") (pin "A") (pinfunction "A1_A") (pintype "passive"))
      (node (ref "SW1") (pin "A'") (pinfunction "A2_A'") (pintype "passive"))
    )
    (net (code "68") (name "SW2") (class "Default")
      (node (ref "C8") (pin "1") (pinfunction "1_1") (pintype "passive"))
      (node (ref "IC2") (pin "40") (pinfunction "PB4_40") (pintype "bidirectional"))
      (node (ref "R13") (pin "2") (pinfunction "2_2") (pintype "passive"))
      (node (ref "SW2") (pin "A") (pinfunction "A1_A") (pintype "passive"))
      (node (ref "SW2") (pin "A'") (pinfunction "A2_A'") (pintype "passive"))
    )
    (net (code "69") (name "SW3") (class "Default")
      (node (ref "C4") (pin "1") (pinfunction "1_1") (pintype "passive"))
      (node (ref "IC2") (pin "20") (pinfunction "PB2_20") (pintype "bidirectional"))
      (node (ref "R1") (pin "2") (pinfunction "2_2") (pintype "passive"))
      (node (ref "SW3") (pin "A") (pinfunction "A1_A") (pintype "passive"))
      (node (ref "SW3") (pin "A'") (pinfunction "A2_A'") (pintype "passive"))
    )
    (net (code "70") (name "SWCLK") (class "Default")
      (node (ref "IC2") (pin "37") (pinfunction "PA14_37") (pintype "bidirectional"))
      (node (ref "R24") (pin "2") (pinfunction "2_2") (pintype "passive"))
    )
    (net (code "71") (name "SWDIO") (class "Default")
      (node (ref "IC2") (pin "34") (pinfunction "PA13_34") (pintype "bidirectional"))
      (node (ref "R23") (pin "2") (pinfunction "2_2") (pintype "passive"))
    )
    (net (code "72") (name "VDDA") (class "Default")
      (node (ref "C31") (pin "1") (pinfunction "1_1") (pintype "passive"))
      (node (ref "C32") (pin "1") (pinfunction "1_1") (pintype "passive"))
      (node (ref "IC2") (pin "9") (pinfunction "VDDA_9") (pintype "power_in"))
      (node (ref "L1") (pin "1") (pinfunction "2_1") (pintype "passive"))
    )
    (net (code "73") (name "unconnected-(IC2-PA2-Pad12)") (class "Default")
      (node (ref "IC2") (pin "12") (pinfunction "PA2_12") (pintype "bidirectional"))
    )
    (net (code "74") (name "unconnected-(IC2-PA3-Pad13)") (class "Default")
      (node (ref "IC2") (pin "13") (pinfunction "PA3_13") (pintype "bidirectional"))
    )
    (net (code "75") (name "unconnected-(IC2-PA11-Pad32)") (class "Default")
      (node (ref "IC2") (pin "32") (pinfunction "PA11_32") (pintype "bidirectional"))
    )
    (net (code "76") (name "unconnected-(IC2-PA12-Pad33)") (class "Default")
      (node (ref "IC2") (pin "33") (pinfunction "PA12_33") (pintype "bidirectional"))
    )
    (net (code "77") (name "unconnected-(IC2-PB0-Pad18)") (class "Default")
      (node (ref "IC2") (pin "18") (pinfunction "PB0_18") (pintype "bidirectional"))
    )
    (net (code "78") (name "unconnected-(IC2-PB1-Pad19)") (class "Default")
      (node (ref "IC2") (pin "19") (pinfunction "PB1_19") (pintype "bidirectional"))
    )
    (net (code "79") (name "unconnected-(IC2-PB3-Pad39)") (class "Default")
      (node (ref "IC2") (pin "39") (pinfunction "PB3_39") (pintype "bidirectional"))
    )
    (net (code "80") (name "unconnected-(IC2-PB8-Pad45)") (class "Default")
      (node (ref "IC2") (pin "45") (pinfunction "PB8_45") (pintype "bidirectional"))
    )
    (net (code "81") (name "unconnected-(IC2-PB9-Pad46)") (class "Default")
      (node (ref "IC2") (pin "46") (pinfunction "PB9_46") (pintype "bidirectional"))
    )
    (net (code "82") (name "unconnected-(IC2-PB10-Pad21)") (class "Default")
      (node (ref "IC2") (pin "21") (pinfunction "PB10_21") (pintype "bidirectional"))
    )
    (net (code "83") (name "unconnected-(IC2-PB11-Pad22)") (class "Default")
      (node (ref "IC2") (pin "22") (pinfunction "PB11_22") (pintype "bidirectional"))
    )
    (net (code "84") (name "unconnected-(IC2-PB12-Pad25)") (class "Default")
      (node (ref "IC2") (pin "25") (pinfunction "PB12_25") (pintype "bidirectional"))
    )
    (net (code "85") (name "unconnected-(IC2-PB13-Pad26)") (class "Default")
      (node (ref "IC2") (pin "26") (pinfunction "PB13_26") (pintype "bidirectional"))
    )
    (net (code "86") (name "unconnected-(IC2-PB14-Pad27)") (class "Default")
      (node (ref "IC2") (pin "27") (pinfunction "PB14_27") (pintype "bidirectional"))
    )
    (net (code "87") (name "unconnected-(IC2-PB15-Pad28)") (class "Default")
      (node (ref "IC2") (pin "28") (pinfunction "PB15_28") (pintype "bidirectional"))
    )
    (net (code "88") (name "unconnected-(IC2-PC13-Pad2)") (class "Default")
      (node (ref "IC2") (pin "2") (pinfunction "PC13_2") (pintype "bidirectional"))
    )
    (net (code "89") (name "unconnected-(IC2-PC14-Pad3)") (class "Default")
      (node (ref "IC2") (pin "3") (pinfunction "PC14_3") (pintype "bidirectional"))
    )
    (net (code "90") (name "unconnected-(IC2-PC15-Pad4)") (class "Default")
      (node (ref "IC2") (pin "4") (pinfunction "PC15_4") (pintype "bidirectional"))
    )
  )
)
